# Gate_Driver_and_Power_Section.net
KiCad netlist of a schematic drawn in Altium Designer
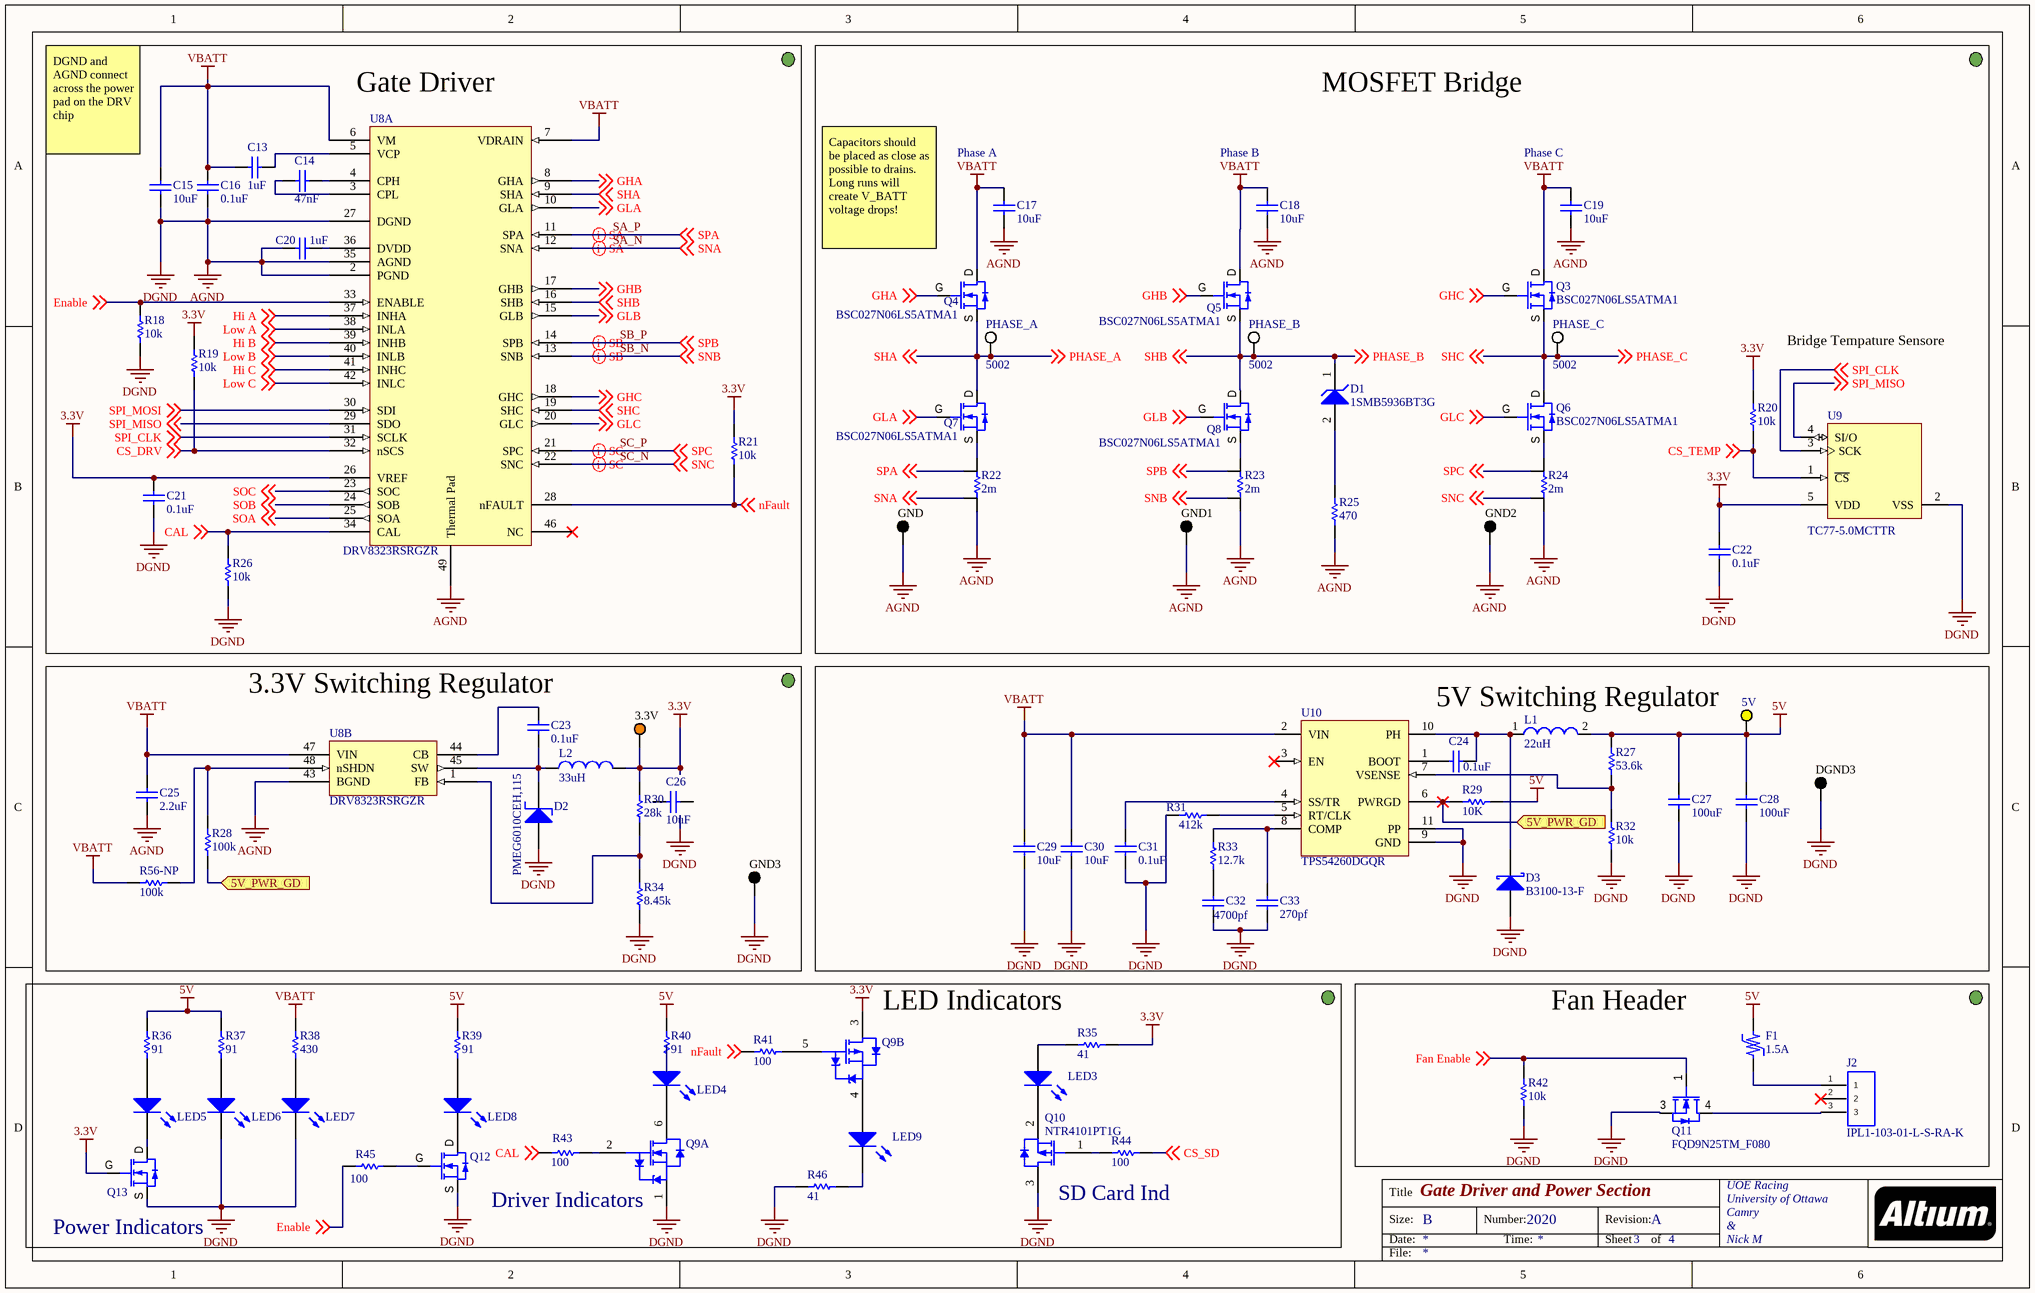
[diagram p0: Gate Driver and Power Section.SchDoc]

(export (version "E")
  (design (tool "Eeschema 10.0.6"))
  (components
    (comp (ref "3.3V")
      (value "5013")
      (footprint "KSTN-5013_V")
      (description "Test Point, Orange, Through Hole, RoHS, Bulk")
      (fields (field (name "MANUFACTURER") "Keystone"))
      (libsource (lib "Altium Content Vault") (part "TESTPOINT_ORANGE"))
    )
    (comp (ref "5V")
      (value "5004")
      (footprint "KSTN-5004")
      (description "Test Point, Yellow, 1-Pin THD, RoHS, Bulk")
      (fields (field (name "MANUFACTURER") "Keystone"))
      (libsource (lib "Altium Content Vault") (part "KSTN-TP-5004"))
    )
    (comp (ref "C13")
      (value "1uF")
      (footprint "CAPC1608X05L")
      (description "CAP CER 1UF 50V X7R 0603")
      (fields
        (field (name "MANUFACTURER") "Taiyo Yuden")
        (field (name "MANUFACTURER PART NUMBER") "GMK107AB7105MAHT")
      )
      (libsource (lib "ECar Reference LIbary") (part "UMK107AB7105KA-T"))
    )
    (comp (ref "C14")
      (value "47nF")
      (footprint "CAPC0603(1608)100_N")
      (description "CAP 47nF 100V ±10% 0603 (1608 Metric) Thickness 1mm SMD")
      (fields (field (name "TOLERANCE") "Â±10%"))
      (libsource (lib "Altium Content Vault") (part "CAP"))
    )
    (comp (ref "C15")
      (value "10uF")
      (footprint "CAPC5750X279X64LL40T39")
      (description "Chip Capacitor, 10 uF, +/- 20%, 100 V, -55 to 125 degC, 2220 (5750 Metric), RoHS, Tape and Reel")
      (fields (field (name "MANUFACTURER") "AVX"))
      (libsource (lib "Altium Content Vault") (part "CAP-NP-2"))
    )
    (comp (ref "C16")
      (value "0.1uF")
      (footprint "CAPC1608X05L")
      (description "CAP ,MIDHIGH VOL,0603,100V,X7R,0.1UF 10% ,T&R")
      (fields (field (name "TOLERANCE") "10%"))
      (libsource (lib "ECar Reference LIbary") (part "HMK107B7104KAHT"))
    )
    (comp (ref "C17")
      (value "10uF")
      (footprint "CAPC5750X279X64NL40T39")
      (description "Chip Capacitor, 10 uF, +/- 20%, 100 V, -55 to 125 degC, 2220 (5750 Metric), RoHS, Tape and Reel")
      (fields (field (name "MANUFACTURER") "AVX"))
      (libsource (lib "Altium Content Vault") (part "CAP-NP-2"))
    )
    (comp (ref "C18")
      (value "10uF")
      (footprint "CAPC5750X279X64NL40T39")
      (description "Chip Capacitor, 10 uF, +/- 20%, 100 V, -55 to 125 degC, 2220 (5750 Metric), RoHS, Tape and Reel")
      (fields (field (name "MANUFACTURER") "AVX"))
      (libsource (lib "Altium Content Vault") (part "CAP-NP-2"))
    )
    (comp (ref "C19")
      (value "10uF")
      (footprint "CAPC5750X279X64NL40T39")
      (description "Chip Capacitor, 10 uF, +/- 20%, 100 V, -55 to 125 degC, 2220 (5750 Metric), RoHS, Tape and Reel")
      (fields (field (name "MANUFACTURER") "AVX"))
      (libsource (lib "Altium Content Vault") (part "CAP-NP-2"))
    )
    (comp (ref "C20")
      (value "1uF")
      (footprint "CAPC1608X05L")
      (description "CAP CER 1UF 50V X7R 0603")
      (fields
        (field (name "MANUFACTURER") "Taiyo Yuden")
        (field (name "MANUFACTURER PART NUMBER") "GMK107AB7105MAHT")
      )
      (libsource (lib "ECar Reference LIbary") (part "UMK107AB7105KA-T"))
    )
    (comp (ref "C21")
      (value "0.1uF")
      (footprint "CAPC1608X05L")
      (description "Cap Ceramic 0.1uF 50V X7R 5% SMD 0603 125C Paper T/R")
      (fields
        (field (name "MANUFACTURER") "Yageo")
        (field (name "MANUFACTURER PART NUMBER") "CC0603JRX7R9BB104")
      )
      (libsource (lib "ECar Reference LIbary") (part "CC0603JRX7R9BB104"))
    )
    (comp (ref "C22")
      (value "0.1uF")
      (footprint "CAPC1608X05L")
      (description "Cap Ceramic 0.1uF 50V X7R 5% SMD 0603 125C Paper T/R")
      (fields
        (field (name "MANUFACTURER") "Yageo")
        (field (name "MANUFACTURER PART NUMBER") "CC0603JRX7R9BB104")
      )
      (libsource (lib "ECar Reference LIbary") (part "CC0603JRX7R9BB104"))
    )
    (comp (ref "C23")
      (value "0.1uF")
      (footprint "CAPC1608X05L")
      (description "Cap Ceramic 0.1uF 50V X7R 5% SMD 0603 125C Paper T/R")
      (fields
        (field (name "MANUFACTURER") "Yageo")
        (field (name "MANUFACTURER PART NUMBER") "CC0603JRX7R9BB104")
      )
      (libsource (lib "ECar Reference LIbary") (part "CC0603JRX7R9BB104"))
    )
    (comp (ref "C24")
      (value "0.1uF")
      (footprint "CAPC1608X05L")
      (description "Cap Ceramic 0.1uF 50V X7R 5% SMD 0603 125C Paper T/R")
      (fields
        (field (name "MANUFACTURER") "Yageo")
        (field (name "MANUFACTURER PART NUMBER") "CC0603JRX7R9BB104")
      )
      (libsource (lib "ECar Reference LIbary") (part "CC0603JRX7R9BB104"))
    )
    (comp (ref "C25")
      (value "2.2uF")
      (footprint "CAPC3225X250X20LL40")
      (description "Chip Capacitor, 2.2 uF, +/- 10%, -55 to 125 degC, 1210 (3225 Metric), RoHS, Tape and Reel")
      (fields
        (field (name "PCN PART NUMBER") "MLCCPartNumberChange30/Nov/2012")
        (field (name "MANUFACTURER") "TDK")
      )
      (libsource (lib "Altium Content Vault") (part "CAP-NP-2"))
    )
    (comp (ref "C26")
      (value "10uF")
      (footprint "CAPC1608X05L")
      (description "Cap Ceramic 10uF 6.3V X5R 20% SMD 0603 85C Paper T/R")
      (fields
        (field (name "MANUFACTURER") "Samsung")
        (field (name "MANUFACTURER PART NUMBER") "CL10A106MQ8NNNC")
      )
      (libsource (lib "ECar Reference LIbary") (part "CL10A106MQ8NNNC"))
    )
    (comp (ref "C27")
      (value "100uF")
      (footprint "MURA-1210_H_2.7_M")
      (description "CAP, Ceramic, 100 uF, 20%, 6.3 V, 1210, RoHS, Tape and Reel")
      (fields (field (name "VOLTAGE") "6.3Vdc") (field (name "TOLERANCE") "20%"))
      (libsource (lib "Altium Content Vault") (part "CAP-NP-2"))
    )
    (comp (ref "C28")
      (value "100uF")
      (footprint "MURA-1210_H_2.7_M")
      (description "CAP, Ceramic, 100 uF, 20%, 6.3 V, 1210, RoHS, Tape and Reel")
      (fields (field (name "VOLTAGE") "6.3Vdc") (field (name "TOLERANCE") "20%"))
      (libsource (lib "Altium Content Vault") (part "CAP-NP-2"))
    )
    (comp (ref "C29")
      (value "10uF")
      (footprint "TDK-C5750-2_L")
      (description "Chip Capacitor, 10 uF, +/- 20%, 100 V, -55 to 125 degC, 2220 (5750 Metric), RoHS, Tape and Reel")
      (fields
        (field (name "PCN PART NUMBER") "MLCCPartNumberChange30/Nov/2012")
        (field (name "MANUFACTURER") "TDK")
      )
      (libsource (lib "Altium Content Vault") (part "CAP-NP-2"))
    )
    (comp (ref "C30")
      (value "10uF")
      (footprint "TDK-C5750-2_L")
      (description "Chip Capacitor, 10 uF, +/- 20%, 100 V, -55 to 125 degC, 2220 (5750 Metric), RoHS, Tape and Reel")
      (fields
        (field (name "PCN PART NUMBER") "MLCCPartNumberChange30/Nov/2012")
        (field (name "MANUFACTURER") "TDK")
      )
      (libsource (lib "Altium Content Vault") (part "CAP-NP-2"))
    )
    (comp (ref "C31")
      (value "0.1uF")
      (footprint "CAPC1608X05L")
      (description "Cap Ceramic 0.1uF 50V X7R 5% SMD 0603 125C Paper T/R")
      (fields
        (field (name "MANUFACTURER") "Yageo")
        (field (name "MANUFACTURER PART NUMBER") "CC0603JRX7R9BB104")
      )
      (libsource (lib "ECar Reference LIbary") (part "CC0603JRX7R9BB104"))
    )
    (comp (ref "C32")
      (value "4700pf")
      (footprint "CAPC1608X90X35ML10T15")
      (fields (field (name "PART NUMBER") "GRM188R72A472KA01D") (field (name "MANUFACTURER") "Murata"))
      (libsource (lib "Altium Content Vault") (part "CAP"))
    )
    (comp (ref "C33")
      (value "270pf")
      (footprint "CAPC1608X90X35ML15T15")
      (fields
        (field (name "MANUFACTURER") "AVX Interconnect / Elco")
        (field (name "PART NUMBER") "06035C271KAT2A")
      )
      (libsource (lib "Altium Content Vault") (part "CAP"))
    )
    (comp (ref "D1")
      (value "1SMB5936BT3G")
      (footprint "ONSC-SMB-2-403A-03_H_V")
      (description "3 W Zener Voltage Regulator, 2-Pin SMB, Pb-Free, Tape and Reel")
      (fields (field (name "MANUFACTURER") "On Semiconductor"))
      (libsource (lib "Altium Content Vault") (part "ONSC-K1A2-2"))
    )
    (comp (ref "D2")
      (value "PMEG6010CEH,115")
      (footprint "SODFL350X120-2N")
      (description "NEXPERIA - PMEG6010CEH,115 - DIODE, SCHOTTKY, 1A, 60V, SOD-123F")
      (libsource (lib "ECar Reference LIbary") (part "PMEG6010CEH,115"))
    )
    (comp (ref "D3")
      (value "B3100-13-F")
      (footprint "DIOD-SMC-2_V")
      (fields (field (name "MANUFACTURER") "DiodesIncorporated"))
      (libsource (lib "Altium Content Vault") (part "DSKY-AK-2"))
    )
    (comp (ref "DGND3")
      (value "5011")
      (footprint "KSTN-5011_V")
      (description "Test Point, Black, Through Hole, RoHS, Bulk")
      (fields (field (name "MANUFACTURER") "Keystone"))
      (libsource (lib "Altium Content Vault") (part "TESTPOINT_BLACK"))
    )
    (comp (ref "F1")
      (value "1.5A")
      (footprint "TECO-NANOSMDC150F-2_V")
      (description "PolySwitch Resettable Device, 6 V, 1.5 A, -40 to 85 degC, 2-Pin SMD, RoHS, Tape and Reel")
      (fields
        (field (name "PART NO") "NANOSMDC150F-2")
        (field (name "MANUFACTURER") "TEConnectivity/CircuitProtection")
      )
      (libsource (lib "Altium Content Vault") (part "PPTC-2"))
    )
    (comp (ref "GND")
      (value "5011")
      (footprint "KSTN-5011_V")
      (description "Test Point, Black, Through Hole, RoHS, Bulk")
      (fields (field (name "MANUFACTURER") "Keystone"))
      (libsource (lib "Altium Content Vault") (part "TESTPOINT_BLACK"))
    )
    (comp (ref "GND1")
      (value "5011")
      (footprint "KSTN-5011_V")
      (description "Test Point, Black, Through Hole, RoHS, Bulk")
      (fields (field (name "MANUFACTURER") "Keystone"))
      (libsource (lib "Altium Content Vault") (part "TESTPOINT_BLACK"))
    )
    (comp (ref "GND2")
      (value "5011")
      (footprint "KSTN-5011_V")
      (description "Test Point, Black, Through Hole, RoHS, Bulk")
      (fields (field (name "MANUFACTURER") "Keystone"))
      (libsource (lib "Altium Content Vault") (part "TESTPOINT_BLACK"))
    )
    (comp (ref "GND3")
      (value "5011")
      (footprint "KSTN-5011_V")
      (description "Test Point, Black, Through Hole, RoHS, Bulk")
      (fields (field (name "MANUFACTURER") "Keystone"))
      (libsource (lib "Altium Content Vault") (part "TESTPOINT_BLACK"))
    )
    (comp (ref "J2")
      (value "IPL1-103-01-L-S-RA-K")
      (footprint "IPL1-103-01-XXX-S-RA")
      (description "CONN HEADER R/A 3POS 2.54MM")
      (libsource (lib "ECar Reference LIbary") (part "IPL1-103-01-L-S-RA-K"))
    )
    (comp (ref "L1")
      (value "22uH")
      (footprint "WE-HCI-1365")
      (description "SMD Flat Wire High Current Inductor WE-HCI, L=22.0 µH")
      (libsource (lib "Altium Content Vault") (part "PAS-IND-INDUCTOR-2"))
    )
    (comp (ref "L2")
      (value "33uH")
      (footprint "INDP8080X46L")
      (description "Fixed Inductors 33uH 30% SMD 8043")
      (fields (field (name "TOLERANCE") "30%"))
      (libsource (lib "ECar Reference LIbary") (part "SRU8043-330Y"))
    )
    (comp (ref "LED3")
      (value "150060VS75000")
      (footprint "0603_A")
      (description "SMD mono-color Chip LED, WL-SMCW, Bright Green")
      (fields (field (name "MANUFACTURER") "Wuerth Elektronik"))
      (libsource (lib "Altium Content Vault") (part "WE-LED_K1A2-2"))
    )
    (comp (ref "LED4")
      (value "150080GS75000")
      (footprint "0805_A")
      (description "SMD mono-color Chip LED, WL-SMCW, Green")
      (fields (field (name "MANUFACTURER") "Wuerth Elektronik"))
      (libsource (lib "Altium Content Vault") (part "WE-LED_K1A2-2"))
    )
    (comp (ref "LED5")
      (value "150080GS75000")
      (footprint "0805_A")
      (description "SMD mono-color Chip LED, WL-SMCW, Green")
      (fields (field (name "MANUFACTURER") "Wuerth Elektronik"))
      (libsource (lib "Altium Content Vault") (part "WE-LED_K1A2-2"))
    )
    (comp (ref "LED6")
      (value "150080GS75000")
      (footprint "0805_A")
      (description "SMD mono-color Chip LED, WL-SMCW, Green")
      (fields (field (name "MANUFACTURER") "Wuerth Elektronik"))
      (libsource (lib "Altium Content Vault") (part "WE-LED_K1A2-2"))
    )
    (comp (ref "LED7")
      (value "150080GS75000")
      (footprint "0805_A")
      (description "SMD mono-color Chip LED, WL-SMCW, Green")
      (fields (field (name "MANUFACTURER") "Wuerth Elektronik"))
      (libsource (lib "Altium Content Vault") (part "WE-LED_K1A2-2"))
    )
    (comp (ref "LED8")
      (value "150080GS75000")
      (footprint "0805_A")
      (description "SMD mono-color Chip LED, WL-SMCW, Green")
      (fields (field (name "MANUFACTURER") "Wuerth Elektronik"))
      (libsource (lib "Altium Content Vault") (part "WE-LED_K1A2-2"))
    )
    (comp (ref "LED9")
      (value "150060VS75000")
      (footprint "0603_A")
      (description "SMD mono-color Chip LED, WL-SMCW, Bright Green")
      (fields (field (name "MANUFACTURER") "Wuerth Elektronik"))
      (libsource (lib "Altium Content Vault") (part "WE-LED_K1A2-2"))
    )
    (comp (ref "PHASE_A")
      (value "5002")
      (footprint "KSTN-5002")
      (description "Test Point, White, 1-Pin THD, RoHS, Bulk")
      (fields (field (name "MANUFACTURER") "KeystoneElectronics"))
      (libsource (lib "Altium Content Vault") (part "KSTN-TP-5002"))
    )
    (comp (ref "PHASE_B")
      (value "5002")
      (footprint "KSTN-5002")
      (description "Test Point, White, 1-Pin THD, RoHS, Bulk")
      (fields (field (name "MANUFACTURER") "KeystoneElectronics"))
      (libsource (lib "Altium Content Vault") (part "KSTN-TP-5002"))
    )
    (comp (ref "PHASE_C")
      (value "5002")
      (footprint "KSTN-5002")
      (description "Test Point, White, 1-Pin THD, RoHS, Bulk")
      (fields (field (name "MANUFACTURER") "KeystoneElectronics"))
      (libsource (lib "Altium Content Vault") (part "KSTN-TP-5002"))
    )
    (comp (ref "Q3")
      (value "BSC027N06LS5ATMA1")
      (footprint "PG-TDSON-8-7")
      (description "MOSFET N-CH 60V 100A 8TDSON")
      (libsource (lib "ECar Reference LIbary") (part "BSC027N06LS5ATMA1"))
    )
    (comp (ref "Q4")
      (value "BSC027N06LS5ATMA1")
      (footprint "PG-TDSON-8-7")
      (description "MOSFET N-CH 60V 100A 8TDSON")
      (libsource (lib "ECar Reference LIbary") (part "BSC027N06LS5ATMA1"))
    )
    (comp (ref "Q5")
      (value "BSC027N06LS5ATMA1")
      (footprint "PG-TDSON-8-7")
      (description "MOSFET N-CH 60V 100A 8TDSON")
      (libsource (lib "ECar Reference LIbary") (part "BSC027N06LS5ATMA1"))
    )
    (comp (ref "Q6")
      (value "BSC027N06LS5ATMA1")
      (footprint "PG-TDSON-8-7")
      (description "MOSFET N-CH 60V 100A 8TDSON")
      (libsource (lib "ECar Reference LIbary") (part "BSC027N06LS5ATMA1"))
    )
    (comp (ref "Q7")
      (value "BSC027N06LS5ATMA1")
      (footprint "PG-TDSON-8-7")
      (description "MOSFET N-CH 60V 100A 8TDSON")
      (libsource (lib "ECar Reference LIbary") (part "BSC027N06LS5ATMA1"))
    )
    (comp (ref "Q8")
      (value "BSC027N06LS5ATMA1")
      (footprint "PG-TDSON-8-7")
      (description "MOSFET N-CH 60V 100A 8TDSON")
      (libsource (lib "ECar Reference LIbary") (part "BSC027N06LS5ATMA1"))
    )
    (comp (ref "Q9")
      (value "NX3008CBKV,115")
      (footprint "NXP-SOT666_M")
      (description "N/P-Channel Trench MOSFET, 30 / -30 V, 400 / -220 mA, -55 to 150 degC, 6-Pin SOT666, Tape and Reel")
      (fields (field (name "MANUFACTURER") "NXP Semiconductors"))
      (libsource (lib "Altium Content Vault") (part "NXP-NPMOS-SGDSGD-6"))
    )
    (comp (ref "Q10")
      (value "NTR4101PT1G")
      (footprint "ONSC-SOT-23-3-318-08_V")
      (description "Trench Power MOSFET, -20 V, Single P-Channel, 3-Pin SOT-23, Pb-Free, Tape and Reel")
      (fields (field (name "MANUFACTURER") "On Semiconductor"))
      (libsource (lib "Altium Content Vault") (part "ONSC-PMOS-G1S2D3-3_D"))
    )
    (comp (ref "Q11")
      (value "FQD9N25TM_F080")
      (footprint "DPAK229P991X239-3N")
      (description "Trans MOSFET N-CH 250V 7.4A 3-Pin(2+Tab) DPAK T/R")
      (fields (field (name "MANUFACTURER") "ON Semiconductor / Fairchild"))
      (libsource (lib "ECar Reference LIbary") (part "FQD9N25TM_F080"))
    )
    (comp (ref "Q12")
      (value "DMN1019USN-7")
      (footprint "SOT95P285X140-3N")
      (description "MOSFET N-CH 12V 9.3A SC59")
      (libsource (lib "ECar Reference LIbary") (part "DMN1019USN-7"))
    )
    (comp (ref "Q13")
      (value "DMN1019USN-7")
      (footprint "SOT95P285X140-3N")
      (description "MOSFET N-CH 12V 9.3A SC59")
      (libsource (lib "ECar Reference LIbary") (part "DMN1019USN-7"))
    )
    (comp (ref "R18")
      (value "10k")
      (footprint "CAPC1608X05L")
      (description "RES SMD 10K OHM 0.5% 1/16W 0816")
      (fields
        (field (name "MANUFACTURER") "Susumu")
        (field (name "MANUFACTURER PART NUMBER") "RR0816P-103-D")
      )
      (libsource (lib "ECar Reference LIbary") (part "RR0816P-103-D"))
    )
    (comp (ref "R19")
      (value "10k")
      (footprint "CAPC1608X05L")
      (description "RES SMD 10K OHM 0.5% 1/16W 0816")
      (fields
        (field (name "MANUFACTURER") "Susumu")
        (field (name "MANUFACTURER PART NUMBER") "RR0816P-103-D")
      )
      (libsource (lib "ECar Reference LIbary") (part "RR0816P-103-D"))
    )
    (comp (ref "R20")
      (value "10k")
      (footprint "CAPC1608X05L")
      (description "RES SMD 10K OHM 0.5% 1/16W 0816")
      (fields
        (field (name "MANUFACTURER") "Susumu")
        (field (name "MANUFACTURER PART NUMBER") "RR0816P-103-D")
      )
      (libsource (lib "ECar Reference LIbary") (part "RR0816P-103-D"))
    )
    (comp (ref "R21")
      (value "10k")
      (footprint "CAPC1608X05L")
      (description "RES SMD 10K OHM 0.5% 1/16W 0816")
      (fields
        (field (name "MANUFACTURER") "Susumu")
        (field (name "MANUFACTURER PART NUMBER") "RR0816P-103-D")
      )
      (libsource (lib "ECar Reference LIbary") (part "RR0816P-103-D"))
    )
    (comp (ref "R22")
      (value "2m")
      (footprint "WSL27262L000FEB")
      (description "RES SMD 2 MOHM 1% 3W 2726")
      (fields (field (name "TOLERANCE") "1%"))
      (libsource (lib "ECar Reference LIbary") (part "WSL27262L000FEB"))
    )
    (comp (ref "R23")
      (value "2m")
      (footprint "WSL27262L000FEB")
      (description "RES SMD 2 MOHM 1% 3W 2726")
      (fields (field (name "TOLERANCE") "1%"))
      (libsource (lib "ECar Reference LIbary") (part "WSL27262L000FEB"))
    )
    (comp (ref "R24")
      (value "2m")
      (footprint "WSL27262L000FEB")
      (description "RES SMD 2 MOHM 1% 3W 2726")
      (fields (field (name "TOLERANCE") "1%"))
      (libsource (lib "ECar Reference LIbary") (part "WSL27262L000FEB"))
    )
    (comp (ref "R25")
      (value "470")
      (footprint "CAPC1608X05L")
      (description "RES SMD 470 OHM 5% 1/10W 0603")
      (fields
        (field (name "MANUFACTURER") "Yageo")
        (field (name "MANUFACTURER PART NUMBER") "RC0603JR-07470RL")
      )
      (libsource (lib "ECar Reference LIbary") (part "RC0603JR-07470RL"))
    )
    (comp (ref "R26")
      (value "10k")
      (footprint "CAPC1608X05L")
      (description "RES SMD 10K OHM 0.5% 1/16W 0816")
      (fields
        (field (name "MANUFACTURER") "Susumu")
        (field (name "MANUFACTURER PART NUMBER") "RR0816P-103-D")
      )
      (libsource (lib "ECar Reference LIbary") (part "RR0816P-103-D"))
    )
    (comp (ref "R27")
      (value "53.6k")
      (footprint "RESC1609X50X30ML10T20")
      (fields (field (name "MANUFACTURER") "Vishay Dale") (field (name "PART NUMBER") "CRCW060353K6FKEA"))
      (libsource (lib "Altium Content Vault") (part "RES"))
    )
    (comp (ref "R28")
      (value "100k")
      (footprint "CAPC1608X05L")
      (description "BOURNS - CR0603-JW-104ELF - RES, 100K, 5%, 0.1W, 0603, THICK FILM")
      (fields (field (name "TOLERANCE") "5%"))
      (libsource (lib "ECar Reference LIbary") (part "CR0603-JW-104ELF"))
    )
    (comp (ref "R29")
      (value "10K")
      (footprint "RESC1608X55X25ML10T15")
      (description "Resistor, 10 KOhm, +/- 5%, 100 mW, -55 to 155 degC, 0603 (1608 Metric), RoHS, Tape and Reel")
      (fields (field (name "MANUFACTURER") "Yageo") (field (name "TOLERANCE") "5%"))
      (libsource (lib "Altium Content Vault") (part "RES-2"))
    )
    (comp (ref "R30")
      (value "28k")
      (footprint "CAPC1608X05L")
      (description "RES SMD 28K OHM 1% 1/10W 0603")
      (fields (field (name "TOLERANCE") "1%"))
      (libsource (lib "ECar Reference LIbary") (part "RMCF0603FT28K0"))
    )
    (comp (ref "R31")
      (value "412k")
      (footprint "RESC1608X55X30LL15T15")
      (fields (field (name "MANUFACTURER") "Panasonic") (field (name "PART NUMBER") "ERJ-3EKF4123V"))
      (libsource (lib "Altium Content Vault") (part "RES"))
    )
    (comp (ref "R32")
      (value "10k")
      (footprint "RESC1609X55X30LL15T15")
      (description "Chip Resistor, 10 KOhm, +/- 1%, 0.1 W, -55 to 155 degC, 0603 (1608 Metric), RoHS, Tape and Reel")
      (fields (field (name "TOLERANCE") "1%") (field (name "MANUFACTURER") "Panasonic"))
      (libsource (lib "Altium Content Vault") (part "RES-2"))
    )
    (comp (ref "R33")
      (value "12.7k")
      (footprint "RESC1608X55X30LL15T15")
      (fields (field (name "MANUFACTURER") "Panasonic") (field (name "PART NUMBER") "ERJ-3EKF1272V"))
      (libsource (lib "Altium Content Vault") (part "RES"))
    )
    (comp (ref "R34")
      (value "8.45k")
      (footprint "CAPC1608X05L")
      (description "RES SMD 8.45K OHM 1% 1/10W 0603")
      (fields (field (name "TOLERANCE") "1%"))
      (libsource (lib "ECar Reference LIbary") (part "RC0603FR-078K45L"))
    )
    (comp (ref "R35")
      (value "41")
      (footprint "RESC1609X50X30ML10T20")
      (fields (field (name "MANUFACTURER") "Vishay Dale") (field (name "PART NUMBER") "CRCW060343R0JNEA"))
      (libsource (lib "Altium Content Vault") (part "RES"))
    )
    (comp (ref "R36")
      (value "91")
      (footprint "RESC1608X50X30NL20T20")
      (fields (field (name "PART NUMBER") "RG1608N-910-B-T5") (field (name "MANUFACTURER") "Susumu"))
      (libsource (lib "Altium Content Vault") (part "RES"))
    )
    (comp (ref "R37")
      (value "91")
      (footprint "RESC1608X50X30NL20T20")
      (fields (field (name "PART NUMBER") "RG1608N-910-B-T5") (field (name "MANUFACTURER") "Susumu"))
      (libsource (lib "Altium Content Vault") (part "RES"))
    )
    (comp (ref "R38")
      (value "430")
      (footprint "RESC1608X55X30LL20T10")
      (fields (field (name "PART NUMBER") "RK73B1JTTD431J") (field (name "MANUFACTURER") "KOA Speer"))
      (libsource (lib "Altium Content Vault") (part "RES"))
    )
    (comp (ref "R39")
      (value "91")
      (footprint "RESC1608X50X30NL20T20")
      (fields (field (name "PART NUMBER") "RG1608N-910-B-T5") (field (name "MANUFACTURER") "Susumu"))
      (libsource (lib "Altium Content Vault") (part "RES"))
    )
    (comp (ref "R40")
      (value "91")
      (footprint "RESC1608X50X30NL20T20")
      (fields (field (name "PART NUMBER") "RG1608N-910-B-T5") (field (name "MANUFACTURER") "Susumu"))
      (libsource (lib "Altium Content Vault") (part "RES"))
    )
    (comp (ref "R41")
      (value "100")
      (footprint "CAPC1608X05L")
      (description "RES SMD 100 OHM 0.5% 1/16W 0816")
      (fields
        (field (name "MANUFACTURER") "Susumu")
        (field (name "MANUFACTURER PART NUMBER") "RR0816P-101-D")
      )
      (libsource (lib "ECar Reference LIbary") (part "RR0816P-101-D"))
    )
    (comp (ref "R42")
      (value "10k")
      (footprint "CAPC1608X05L")
      (description "RES SMD 10K OHM 0.5% 1/16W 0816")
      (fields
        (field (name "MANUFACTURER") "Susumu")
        (field (name "MANUFACTURER PART NUMBER") "RR0816P-103-D")
      )
      (libsource (lib "ECar Reference LIbary") (part "RR0816P-103-D"))
    )
    (comp (ref "R43")
      (value "100")
      (footprint "CAPC1608X05L")
      (description "RES SMD 100 OHM 0.5% 1/16W 0816")
      (fields
        (field (name "MANUFACTURER") "Susumu")
        (field (name "MANUFACTURER PART NUMBER") "RR0816P-101-D")
      )
      (libsource (lib "ECar Reference LIbary") (part "RR0816P-101-D"))
    )
    (comp (ref "R44")
      (value "100")
      (footprint "CAPC1608X05L")
      (description "RES SMD 100 OHM 0.5% 1/16W 0816")
      (fields
        (field (name "MANUFACTURER") "Susumu")
        (field (name "MANUFACTURER PART NUMBER") "RR0816P-101-D")
      )
      (libsource (lib "ECar Reference LIbary") (part "RR0816P-101-D"))
    )
    (comp (ref "R45")
      (value "100")
      (footprint "CAPC1608X05L")
      (description "RES SMD 100 OHM 0.5% 1/16W 0816")
      (fields
        (field (name "MANUFACTURER") "Susumu")
        (field (name "MANUFACTURER PART NUMBER") "RR0816P-101-D")
      )
      (libsource (lib "ECar Reference LIbary") (part "RR0816P-101-D"))
    )
    (comp (ref "R46")
      (value "41")
      (footprint "RESC1609X50X30ML10T20")
      (fields (field (name "MANUFACTURER") "Vishay Dale") (field (name "PART NUMBER") "CRCW060343R0JNEA"))
      (libsource (lib "Altium Content Vault") (part "RES"))
    )
    (comp (ref "R56-NP")
      (value "100k")
      (footprint "CAPC1608X05L")
      (description "BOURNS - CR0603-JW-104ELF - RES, 100K, 5%, 0.1W, 0603, THICK FILM")
      (fields (field (name "TOLERANCE") "5%"))
      (libsource (lib "ECar Reference LIbary") (part "CR0603-JW-104ELF"))
    )
    (comp (ref "U8")
      (value "DRV8323RSRGZR")
      (footprint "QFN50P700X700X100_HS-49N")
      (description "IC 3PHASE GATE DRIVER 48VQFN")
      (fields (field (name "MANUFACTURER") "Texas Instruments"))
      (libsource (lib "ECar Reference LIbary") (part "DRV8323RSRGZR"))
    )
    (comp (ref "U9")
      (value "TC77-5.0MCTTR")
      (footprint "SOT-23-CT5_N")
      (description "Thermal Sensor with SPI Interface, 5-Pin SOT-23, -55°C to +125°C Temperature, Tape and Reel")
      (libsource (lib "Altium Content Vault") (part "SEN-TEMP-TC77-5"))
    )
    (comp (ref "U10")
      (value "TPS54260DGQR")
      (footprint "DGQ0010D_N")
      (fields (field (name "MANUFACTURER") "Texas Instruments"))
      (libsource (lib "Altium Content Vault") (part "TI-TPS54260DGQ10-1675X1445TP"))
    )
  )
  (nets
    (net (code "1") (name "/5V_PWR_GD") (class "Default")
      (node (ref "R28") (pin "1") (pinfunction "1_1") (pintype "passive"))
      (node (ref "R29") (pin "1") (pinfunction "1_1") (pintype "passive"))
      (node (ref "U10") (pin "6") (pinfunction "PWRGD_6") (pintype "open_collector"))
    )
    (net (code "2") (name "3.3V") (class "Default")
      (node (ref "3.3V") (pin "1") (pinfunction "1_1") (pintype "passive"))
      (node (ref "C21") (pin "2") (pinfunction "2_2") (pintype "passive"))
      (node (ref "C22") (pin "2") (pinfunction "2_2") (pintype "passive"))
      (node (ref "L2") (pin "2") (pinfunction "2_2") (pintype "passive"))
      (node (ref "Q13") (pin "G") (pinfunction "G_G") (pintype "passive"))
      (node (ref "Q9") (pin "3") (pinfunction "D2_3") (pintype "passive"))
      (node (ref "R19") (pin "2") (pinfunction "2_2") (pintype "passive"))
      (node (ref "R20") (pin "2") (pinfunction "2_2") (pintype "passive"))
      (node (ref "R21") (pin "2") (pinfunction "2_2") (pintype "passive"))
      (node (ref "R30") (pin "2") (pinfunction "2_2") (pintype "passive"))
      (node (ref "R35") (pin "1") (pinfunction "1_1") (pintype "passive"))
      (node (ref "U8") (pin "26") (pinfunction "VREF_26") (pintype "power_in"))
      (node (ref "U9") (pin "5") (pinfunction "VDD_5") (pintype "power_in"))
    )
    (net (code "3") (name "5V") (class "Default")
      (node (ref "5V") (pin "1") (pinfunction "1_1") (pintype "passive"))
      (node (ref "C27") (pin "2") (pinfunction "2_2") (pintype "passive"))
      (node (ref "C28") (pin "2") (pinfunction "2_2") (pintype "passive"))
      (node (ref "F1") (pin "2") (pinfunction "2_2") (pintype "passive"))
      (node (ref "L1") (pin "2") (pinfunction "2_2") (pintype "passive"))
      (node (ref "R27") (pin "2") (pinfunction "2_2") (pintype "passive"))
      (node (ref "R29") (pin "2") (pinfunction "2_2") (pintype "passive"))
      (node (ref "R36") (pin "2") (pinfunction "2_2") (pintype "passive"))
      (node (ref "R37") (pin "2") (pinfunction "2_2") (pintype "passive"))
      (node (ref "R39") (pin "2") (pinfunction "2_2") (pintype "passive"))
      (node (ref "R40") (pin "2") (pinfunction "2_2") (pintype "passive"))
    )
    (net (code "4") (name "AGND") (class "Default")
      (node (ref "C15") (pin "1") (pinfunction "1_1") (pintype "passive"))
      (node (ref "C16") (pin "1") (pinfunction "1_1") (pintype "passive"))
      (node (ref "C17") (pin "1") (pinfunction "1_1") (pintype "passive"))
      (node (ref "C18") (pin "1") (pinfunction "1_1") (pintype "passive"))
      (node (ref "C19") (pin "1") (pinfunction "1_1") (pintype "passive"))
      (node (ref "C20") (pin "1") (pinfunction "1_1") (pintype "passive"))
      (node (ref "C21") (pin "1") (pinfunction "1_1") (pintype "passive"))
      (node (ref "C22") (pin "1") (pinfunction "1_1") (pintype "passive"))
      (node (ref "C25") (pin "1") (pinfunction "1_1") (pintype "passive"))
      (node (ref "C27") (pin "1") (pinfunction "1_1") (pintype "passive"))
      (node (ref "C28") (pin "1") (pinfunction "1_1") (pintype "passive"))
      (node (ref "C29") (pin "1") (pinfunction "1_1") (pintype "passive"))
      (node (ref "C30") (pin "1") (pinfunction "1_1") (pintype "passive"))
      (node (ref "C31") (pin "1") (pinfunction "1_1") (pintype "passive"))
      (node (ref "C32") (pin "1") (pinfunction "1_1") (pintype "passive"))
      (node (ref "C33") (pin "1") (pinfunction "1_1") (pintype "passive"))
      (node (ref "D2") (pin "2") (pinfunction "A_2") (pintype "passive"))
      (node (ref "D3") (pin "1") (pinfunction "A_1") (pintype "passive"))
      (node (ref "DGND3") (pin "1") (pinfunction "1_1") (pintype "passive"))
      (node (ref "GND") (pin "1") (pinfunction "1_1") (pintype "passive"))
      (node (ref "GND1") (pin "1") (pinfunction "1_1") (pintype "passive"))
      (node (ref "GND2") (pin "1") (pinfunction "1_1") (pintype "passive"))
      (node (ref "GND3") (pin "1") (pinfunction "1_1") (pintype "passive"))
      (node (ref "LED6") (pin "1") (pinfunction "K_1") (pintype "passive"))
      (node (ref "LED7") (pin "1") (pinfunction "K_1") (pintype "passive"))
      (node (ref "Q10") (pin "3") (pinfunction "D_3") (pintype "passive"))
      (node (ref "Q11") (pin "3") (pinfunction "S_3") (pintype "passive"))
      (node (ref "Q12") (pin "S") (pinfunction "S_S") (pintype "passive"))
      (node (ref "Q13") (pin "S") (pinfunction "S_S") (pintype "passive"))
      (node (ref "Q9") (pin "1") (pinfunction "S1_1") (pintype "passive"))
      (node (ref "R18") (pin "1") (pinfunction "1_1") (pintype "passive"))
      (node (ref "R22") (pin "3") (pinfunction "3_3") (pintype "passive"))
      (node (ref "R23") (pin "3") (pinfunction "3_3") (pintype "passive"))
      (node (ref "R24") (pin "3") (pinfunction "3_3") (pintype "passive"))
      (node (ref "R25") (pin "2") (pinfunction "2_2") (pintype "passive"))
      (node (ref "R26") (pin "1") (pinfunction "1_1") (pintype "passive"))
      (node (ref "R31") (pin "1") (pinfunction "1_1") (pintype "passive"))
      (node (ref "R32") (pin "1") (pinfunction "1_1") (pintype "passive"))
      (node (ref "R34") (pin "1") (pinfunction "1_1") (pintype "passive"))
      (node (ref "R42") (pin "1") (pinfunction "1_1") (pintype "passive"))
      (node (ref "R46") (pin "2") (pinfunction "2_2") (pintype "passive"))
      (node (ref "U10") (pin "11") (pinfunction "PP_11") (pintype "power_in"))
      (node (ref "U10") (pin "9") (pinfunction "GND_9") (pintype "power_in"))
      (node (ref "U8") (pin "2") (pinfunction "PGND_2") (pintype "power_in"))
      (node (ref "U8") (pin "27") (pinfunction "DGND_27") (pintype "power_in"))
      (node (ref "U8") (pin "35") (pinfunction "AGND_35") (pintype "power_in"))
      (node (ref "U8") (pin "43") (pinfunction "BGND_43") (pintype "power_in"))
      (node (ref "U8") (pin "49") (pinfunction "Thermal_Pad_49") (pintype "passive"))
      (node (ref "U9") (pin "2") (pinfunction "VSS_2") (pintype "power_in"))
    )
    (net (code "5") (name "CAL") (class "Default")
      (node (ref "R26") (pin "2") (pinfunction "2_2") (pintype "passive"))
      (node (ref "R43") (pin "1") (pinfunction "1_1") (pintype "passive"))
      (node (ref "U8") (pin "34") (pinfunction "CAL_34") (pintype "power_in"))
    )
    (net (code "6") (name "CS_DRV") (class "Default")
      (node (ref "R19") (pin "1") (pinfunction "1_1") (pintype "passive"))
      (node (ref "U8") (pin "32") (pinfunction "nSCS_32") (pintype "input"))
    )
    (net (code "7") (name "CS_SD") (class "Default")
      (node (ref "R44") (pin "2") (pinfunction "2_2") (pintype "passive"))
    )
    (net (code "8") (name "CS_TEMP") (class "Default")
      (node (ref "R20") (pin "1") (pinfunction "1_1") (pintype "passive"))
      (node (ref "U9") (pin "1") (pinfunction "~{CS}_1") (pintype "input"))
    )
    (net (code "9") (name "Enable") (class "Default")
      (node (ref "R18") (pin "2") (pinfunction "2_2") (pintype "passive"))
      (node (ref "R45") (pin "1") (pinfunction "1_1") (pintype "passive"))
      (node (ref "U8") (pin "33") (pinfunction "ENABLE_33") (pintype "input"))
    )
    (net (code "10") (name "Fan Enable") (class "Default")
      (node (ref "Q11") (pin "1") (pinfunction "G_1") (pintype "passive"))
      (node (ref "R42") (pin "2") (pinfunction "2_2") (pintype "passive"))
    )
    (net (code "11") (name "GHA") (class "Default")
      (node (ref "Q4") (pin "G") (pinfunction "G_G") (pintype "passive"))
      (node (ref "U8") (pin "8") (pinfunction "GHA_8") (pintype "output"))
    )
    (net (code "12") (name "GHB") (class "Default")
      (node (ref "Q5") (pin "G") (pinfunction "G_G") (pintype "passive"))
      (node (ref "U8") (pin "17") (pinfunction "GHB_17") (pintype "output"))
    )
    (net (code "13") (name "GHC") (class "Default")
      (node (ref "Q3") (pin "G") (pinfunction "G_G") (pintype "passive"))
      (node (ref "U8") (pin "18") (pinfunction "GHC_18") (pintype "output"))
    )
    (net (code "14") (name "GLA") (class "Default")
      (node (ref "Q7") (pin "G") (pinfunction "G_G") (pintype "passive"))
      (node (ref "U8") (pin "10") (pinfunction "GLA_10") (pintype "output"))
    )
    (net (code "15") (name "GLB") (class "Default")
      (node (ref "Q8") (pin "G") (pinfunction "G_G") (pintype "passive"))
      (node (ref "U8") (pin "15") (pinfunction "GLB_15") (pintype "output"))
    )
    (net (code "16") (name "GLC") (class "Default")
      (node (ref "Q6") (pin "G") (pinfunction "G_G") (pintype "passive"))
      (node (ref "U8") (pin "20") (pinfunction "GLC_20") (pintype "output"))
    )
    (net (code "17") (name "Hi A") (class "Default")
      (node (ref "U8") (pin "37") (pinfunction "INHA_37") (pintype "input"))
    )
    (net (code "18") (name "Hi B") (class "Default")
      (node (ref "U8") (pin "39") (pinfunction "INHB_39") (pintype "input"))
    )
    (net (code "19") (name "Hi C") (class "Default")
      (node (ref "U8") (pin "41") (pinfunction "INHC_41") (pintype "input"))
    )
    (net (code "20") (name "Low A") (class "Default")
      (node (ref "U8") (pin "38") (pinfunction "INLA_38") (pintype "input"))
    )
    (net (code "21") (name "Low B") (class "Default")
      (node (ref "U8") (pin "40") (pinfunction "INLB_40") (pintype "input"))
    )
    (net (code "22") (name "Low C") (class "Default")
      (node (ref "U8") (pin "42") (pinfunction "INLC_42") (pintype "input"))
    )
    (net (code "23") (name "Net-(C32-Pad2)") (class "Default")
      (node (ref "C32") (pin "2") (pinfunction "2_2") (pintype "passive"))
      (node (ref "R33") (pin "2") (pinfunction "2_2") (pintype "passive"))
    )
    (net (code "24") (name "Net-(D1-A)") (class "Default")
      (node (ref "D1") (pin "2") (pinfunction "A_2") (pintype "passive"))
      (node (ref "R25") (pin "1") (pinfunction "1_1") (pintype "passive"))
    )
    (net (code "25") (name "Net-(D2-K)") (class "Default")
      (node (ref "C23") (pin "1") (pinfunction "1_1") (pintype "passive"))
      (node (ref "D2") (pin "1") (pinfunction "K_1") (pintype "passive"))
      (node (ref "L2") (pin "1") (pinfunction "1_1") (pintype "passive"))
      (node (ref "U8") (pin "45") (pinfunction "SW_45") (pintype "output"))
    )
    (net (code "26") (name "Net-(D3-K)") (class "Default")
      (node (ref "C24") (pin "2") (pinfunction "2_2") (pintype "passive"))
      (node (ref "D3") (pin "2") (pinfunction "K_2") (pintype "passive"))
      (node (ref "L1") (pin "1") (pinfunction "1_1") (pintype "passive"))
      (node (ref "U10") (pin "10") (pinfunction "PH_10") (pintype "power_in"))
    )
    (net (code "27") (name "Net-(F1-Pad1)") (class "Default")
      (node (ref "F1") (pin "1") (pinfunction "1_1") (pintype "passive"))
      (node (ref "J2") (pin "1") (pinfunction "1_1") (pintype "passive"))
    )
    (net (code "28") (name "Net-(LED3-A)") (class "Default")
      (node (ref "LED3") (pin "2") (pinfunction "A_2") (pintype "passive"))
      (node (ref "R35") (pin "2") (pinfunction "2_2") (pintype "passive"))
    )
    (net (code "29") (name "Net-(LED3-K)") (class "Default")
      (node (ref "LED3") (pin "1") (pinfunction "K_1") (pintype "passive"))
      (node (ref "Q10") (pin "2") (pinfunction "S_2") (pintype "passive"))
    )
    (net (code "30") (name "Net-(LED4-A)") (class "Default")
      (node (ref "LED4") (pin "2") (pinfunction "A_2") (pintype "passive"))
      (node (ref "R40") (pin "1") (pinfunction "1_1") (pintype "passive"))
    )
    (net (code "31") (name "Net-(LED4-K)") (class "Default")
      (node (ref "LED4") (pin "1") (pinfunction "K_1") (pintype "passive"))
      (node (ref "Q9") (pin "6") (pinfunction "D1_6") (pintype "passive"))
    )
    (net (code "32") (name "Net-(LED5-A)") (class "Default")
      (node (ref "LED5") (pin "2") (pinfunction "A_2") (pintype "passive"))
      (node (ref "R36") (pin "1") (pinfunction "1_1") (pintype "passive"))
    )
    (net (code "33") (name "Net-(LED5-K)") (class "Default")
      (node (ref "LED5") (pin "1") (pinfunction "K_1") (pintype "passive"))
      (node (ref "Q13") (pin "D") (pinfunction "D_D") (pintype "passive"))
    )
    (net (code "34") (name "Net-(LED6-A)") (class "Default")
      (node (ref "LED6") (pin "2") (pinfunction "A_2") (pintype "passive"))
      (node (ref "R37") (pin "1") (pinfunction "1_1") (pintype "passive"))
    )
    (net (code "35") (name "Net-(LED7-A)") (class "Default")
      (node (ref "LED7") (pin "2") (pinfunction "A_2") (pintype "passive"))
      (node (ref "R38") (pin "1") (pinfunction "1_1") (pintype "passive"))
    )
    (net (code "36") (name "Net-(LED8-A)") (class "Default")
      (node (ref "LED8") (pin "2") (pinfunction "A_2") (pintype "passive"))
      (node (ref "R39") (pin "1") (pinfunction "1_1") (pintype "passive"))
    )
    (net (code "37") (name "Net-(LED8-K)") (class "Default")
      (node (ref "LED8") (pin "1") (pinfunction "K_1") (pintype "passive"))
      (node (ref "Q12") (pin "D") (pinfunction "D_D") (pintype "passive"))
    )
    (net (code "38") (name "Net-(LED9-A)") (class "Default")
      (node (ref "LED9") (pin "2") (pinfunction "A_2") (pintype "passive"))
      (node (ref "Q9") (pin "4") (pinfunction "S2_4") (pintype "passive"))
    )
    (net (code "39") (name "Net-(LED9-K)") (class "Default")
      (node (ref "LED9") (pin "1") (pinfunction "K_1") (pintype "passive"))
      (node (ref "R46") (pin "1") (pinfunction "1_1") (pintype "passive"))
    )
    (net (code "40") (name "Net-(Q6-PadS)") (class "Default")
      (node (ref "Q6") (pin "S") (pinfunction "S_S") (pintype "passive"))
      (node (ref "R24") (pin "1") (pinfunction "1_1") (pintype "passive"))
    )
    (net (code "41") (name "Net-(Q7-PadS)") (class "Default")
      (node (ref "Q7") (pin "S") (pinfunction "S_S") (pintype "passive"))
      (node (ref "R22") (pin "1") (pinfunction "1_1") (pintype "passive"))
    )
    (net (code "42") (name "Net-(Q8-PadS)") (class "Default")
      (node (ref "Q8") (pin "S") (pinfunction "S_S") (pintype "passive"))
      (node (ref "R23") (pin "1") (pinfunction "1_1") (pintype "passive"))
    )
    (net (code "43") (name "Net-(Q9A-G1)") (class "Default")
      (node (ref "Q9") (pin "2") (pinfunction "G1_2") (pintype "passive"))
      (node (ref "R43") (pin "2") (pinfunction "2_2") (pintype "passive"))
    )
    (net (code "44") (name "Net-(Q9B-G2)") (class "Default")
      (node (ref "Q9") (pin "5") (pinfunction "G2_5") (pintype "passive"))
      (node (ref "R41") (pin "2") (pinfunction "2_2") (pintype "passive"))
    )
    (net (code "45") (name "Net-(Q10-G)") (class "Default")
      (node (ref "Q10") (pin "1") (pinfunction "G_1") (pintype "passive"))
      (node (ref "R44") (pin "1") (pinfunction "1_1") (pintype "passive"))
    )
    (net (code "46") (name "Net-(Q11-D)") (class "Default")
      (node (ref "J2") (pin "3") (pinfunction "3_3") (pintype "passive"))
      (node (ref "Q11") (pin "4") (pinfunction "D_4") (pintype "passive"))
    )
    (net (code "47") (name "Net-(Q12-PadG)") (class "Default")
      (node (ref "Q12") (pin "G") (pinfunction "G_G") (pintype "passive"))
      (node (ref "R45") (pin "2") (pinfunction "2_2") (pintype "passive"))
    )
    (net (code "48") (name "Net-(U8A-CPH)") (class "Default")
      (node (ref "C14") (pin "2") (pinfunction "2_2") (pintype "passive"))
      (node (ref "U8") (pin "4") (pinfunction "CPH_4") (pintype "power_in"))
    )
    (net (code "49") (name "Net-(U8A-CPL)") (class "Default")
      (node (ref "C14") (pin "1") (pinfunction "1_1") (pintype "passive"))
      (node (ref "U8") (pin "3") (pinfunction "CPL_3") (pintype "power_in"))
    )
    (net (code "50") (name "Net-(U8A-DVDD)") (class "Default")
      (node (ref "C20") (pin "2") (pinfunction "2_2") (pintype "passive"))
      (node (ref "U8") (pin "36") (pinfunction "DVDD_36") (pintype "power_in"))
    )
    (net (code "51") (name "Net-(U8A-VCP)") (class "Default")
      (node (ref "C13") (pin "2") (pinfunction "2_2") (pintype "passive"))
      (node (ref "U8") (pin "5") (pinfunction "VCP_5") (pintype "power_in"))
    )
    (net (code "52") (name "Net-(U8B-CB)") (class "Default")
      (node (ref "C23") (pin "2") (pinfunction "2_2") (pintype "passive"))
      (node (ref "U8") (pin "44") (pinfunction "CB_44") (pintype "power_in"))
    )
    (net (code "53") (name "Net-(U8B-FB)") (class "Default")
      (node (ref "R30") (pin "1") (pinfunction "1_1") (pintype "passive"))
      (node (ref "R34") (pin "2") (pinfunction "2_2") (pintype "passive"))
      (node (ref "U8") (pin "1") (pinfunction "FB_1") (pintype "input"))
    )
    (net (code "54") (name "Net-(U8B-nSHDN)") (class "Default")
      (node (ref "R28") (pin "2") (pinfunction "2_2") (pintype "passive"))
      (node (ref "R56-NP") (pin "2") (pinfunction "2_2") (pintype "passive"))
      (node (ref "U8") (pin "48") (pinfunction "nSHDN_48") (pintype "input"))
    )
    (net (code "55") (name "Net-(U10-BOOT)") (class "Default")
      (node (ref "C24") (pin "1") (pinfunction "1_1") (pintype "passive"))
      (node (ref "U10") (pin "1") (pinfunction "BOOT_1") (pintype "passive"))
    )
    (net (code "56") (name "Net-(U10-COMP)") (class "Default")
      (node (ref "C33") (pin "2") (pinfunction "2_2") (pintype "passive"))
      (node (ref "R33") (pin "1") (pinfunction "1_1") (pintype "passive"))
      (node (ref "U10") (pin "8") (pinfunction "COMP_8") (pintype "passive"))
    )
    (net (code "57") (name "Net-(U10-RT{slash}CLK)") (class "Default")
      (node (ref "R31") (pin "2") (pinfunction "2_2") (pintype "passive"))
      (node (ref "U10") (pin "5") (pinfunction "RT/CLK_5") (pintype "input"))
    )
    (net (code "58") (name "Net-(U10-SS{slash}TR)") (class "Default")
      (node (ref "C31") (pin "2") (pinfunction "2_2") (pintype "passive"))
      (node (ref "U10") (pin "4") (pinfunction "SS/TR_4") (pintype "input"))
    )
    (net (code "59") (name "Net-(U10-VSENSE)") (class "Default")
      (node (ref "R27") (pin "1") (pinfunction "1_1") (pintype "passive"))
      (node (ref "R32") (pin "2") (pinfunction "2_2") (pintype "passive"))
      (node (ref "U10") (pin "7") (pinfunction "VSENSE_7") (pintype "input"))
    )
    (net (code "60") (name "PHASE_A") (class "Default")
      (node (ref "PHASE_A") (pin "1") (pintype "passive"))
      (node (ref "Q4") (pin "S") (pinfunction "S_S") (pintype "passive"))
      (node (ref "Q7") (pin "D") (pinfunction "D_D") (pintype "passive"))
      (node (ref "U8") (pin "9") (pinfunction "SHA_9") (pintype "input"))
    )
    (net (code "61") (name "PHASE_B") (class "Default")
      (node (ref "D1") (pin "1") (pinfunction "K_1") (pintype "passive"))
      (node (ref "PHASE_B") (pin "1") (pintype "passive"))
      (node (ref "Q5") (pin "S") (pinfunction "S_S") (pintype "passive"))
      (node (ref "Q8") (pin "D") (pinfunction "D_D") (pintype "passive"))
      (node (ref "U8") (pin "16") (pinfunction "SHB_16") (pintype "input"))
    )
    (net (code "62") (name "PHASE_C") (class "Default")
      (node (ref "PHASE_C") (pin "1") (pintype "passive"))
      (node (ref "Q3") (pin "S") (pinfunction "S_S") (pintype "passive"))
      (node (ref "Q6") (pin "D") (pinfunction "D_D") (pintype "passive"))
      (node (ref "U8") (pin "19") (pinfunction "SHC_19") (pintype "input"))
    )
    (net (code "63") (name "SNA") (class "Default")
      (node (ref "R22") (pin "4") (pinfunction "4_4") (pintype "passive"))
      (node (ref "U8") (pin "12") (pinfunction "SNA_12") (pintype "input"))
    )
    (net (code "64") (name "SNB") (class "Default")
      (node (ref "R23") (pin "4") (pinfunction "4_4") (pintype "passive"))
      (node (ref "U8") (pin "13") (pinfunction "SNB_13") (pintype "input"))
    )
    (net (code "65") (name "SNC") (class "Default")
      (node (ref "R24") (pin "4") (pinfunction "4_4") (pintype "passive"))
      (node (ref "U8") (pin "22") (pinfunction "SNC_22") (pintype "input"))
    )
    (net (code "66") (name "SOA") (class "Default")
      (node (ref "U8") (pin "25") (pinfunction "SOA_25") (pintype "output"))
    )
    (net (code "67") (name "SOB") (class "Default")
      (node (ref "U8") (pin "24") (pinfunction "SOB_24") (pintype "output"))
    )
    (net (code "68") (name "SOC") (class "Default")
      (node (ref "U8") (pin "23") (pinfunction "SOC_23") (pintype "output"))
    )
    (net (code "69") (name "SPA") (class "Default")
      (node (ref "R22") (pin "2") (pinfunction "2_2") (pintype "passive"))
      (node (ref "U8") (pin "11") (pinfunction "SPA_11") (pintype "input"))
    )
    (net (code "70") (name "SPB") (class "Default")
      (node (ref "R23") (pin "2") (pinfunction "2_2") (pintype "passive"))
      (node (ref "U8") (pin "14") (pinfunction "SPB_14") (pintype "input"))
    )
    (net (code "71") (name "SPC") (class "Default")
      (node (ref "R24") (pin "2") (pinfunction "2_2") (pintype "passive"))
      (node (ref "U8") (pin "21") (pinfunction "SPC_21") (pintype "input"))
    )
    (net (code "72") (name "SPI_CLK") (class "Default")
      (node (ref "U8") (pin "31") (pinfunction "SCLK_31") (pintype "input"))
      (node (ref "U9") (pin "3") (pinfunction "SCK_3") (pintype "input"))
    )
    (net (code "73") (name "SPI_MISO") (class "Default")
      (node (ref "U8") (pin "29") (pinfunction "SDO_29") (pintype "open_collector"))
      (node (ref "U9") (pin "4") (pinfunction "SI/O_4") (pintype "bidirectional"))
    )
    (net (code "74") (name "SPI_MOSI") (class "Default")
      (node (ref "U8") (pin "30") (pinfunction "SDI_30") (pintype "input"))
    )
    (net (code "75") (name "VBATT") (class "Default")
      (node (ref "C13") (pin "1") (pinfunction "1_1") (pintype "passive"))
      (node (ref "C15") (pin "2") (pinfunction "2_2") (pintype "passive"))
      (node (ref "C16") (pin "2") (pinfunction "2_2") (pintype "passive"))
      (node (ref "C17") (pin "2") (pinfunction "2_2") (pintype "passive"))
      (node (ref "C18") (pin "2") (pinfunction "2_2") (pintype "passive"))
      (node (ref "C19") (pin "2") (pinfunction "2_2") (pintype "passive"))
      (node (ref "C25") (pin "2") (pinfunction "2_2") (pintype "passive"))
      (node (ref "C29") (pin "2") (pinfunction "2_2") (pintype "passive"))
      (node (ref "C30") (pin "2") (pinfunction "2_2") (pintype "passive"))
      (node (ref "Q3") (pin "D") (pinfunction "D_D") (pintype "passive"))
      (node (ref "Q4") (pin "D") (pinfunction "D_D") (pintype "passive"))
      (node (ref "Q5") (pin "D") (pinfunction "D_D") (pintype "passive"))
      (node (ref "R38") (pin "2") (pinfunction "2_2") (pintype "passive"))
      (node (ref "R56-NP") (pin "1") (pinfunction "1_1") (pintype "passive"))
      (node (ref "U10") (pin "2") (pinfunction "VIN_2") (pintype "power_in"))
      (node (ref "U8") (pin "47") (pinfunction "VIN_47") (pintype "power_in"))
      (node (ref "U8") (pin "6") (pinfunction "VM_6") (pintype "power_in"))
      (node (ref "U8") (pin "7") (pinfunction "VDRAIN_7") (pintype "input"))
    )
    (net (code "76") (name "nFault") (class "Default")
      (node (ref "R21") (pin "1") (pinfunction "1_1") (pintype "passive"))
      (node (ref "R41") (pin "1") (pinfunction "1_1") (pintype "passive"))
      (node (ref "U8") (pin "28") (pinfunction "nFAULT_28") (pintype "open_collector"))
    )
    (net (code "77") (name "unconnected-(C26-Pad1)") (class "Default")
      (node (ref "C26") (pin "1") (pinfunction "1_1") (pintype "passive"))
    )
    (net (code "78") (name "unconnected-(C26-Pad2)") (class "Default")
      (node (ref "C26") (pin "2") (pinfunction "2_2") (pintype "passive"))
    )
    (net (code "79") (name "unconnected-(J2-Pad2)") (class "Default")
      (node (ref "J2") (pin "2") (pinfunction "2_2") (pintype "passive+no_connect"))
    )
    (net (code "80") (name "unconnected-(U8A-NC-Pad46)") (class "Default")
      (node (ref "U8") (pin "46") (pinfunction "NC_46") (pintype "tri_state+no_connect"))
    )
    (net (code "81") (name "unconnected-(U10-EN-Pad3)") (class "Default")
      (node (ref "U10") (pin "3") (pinfunction "EN_3") (pintype "input+no_connect"))
    )
  )
)
